# Sheet4.net
KiCad netlist of a schematic drawn in Altium Designer
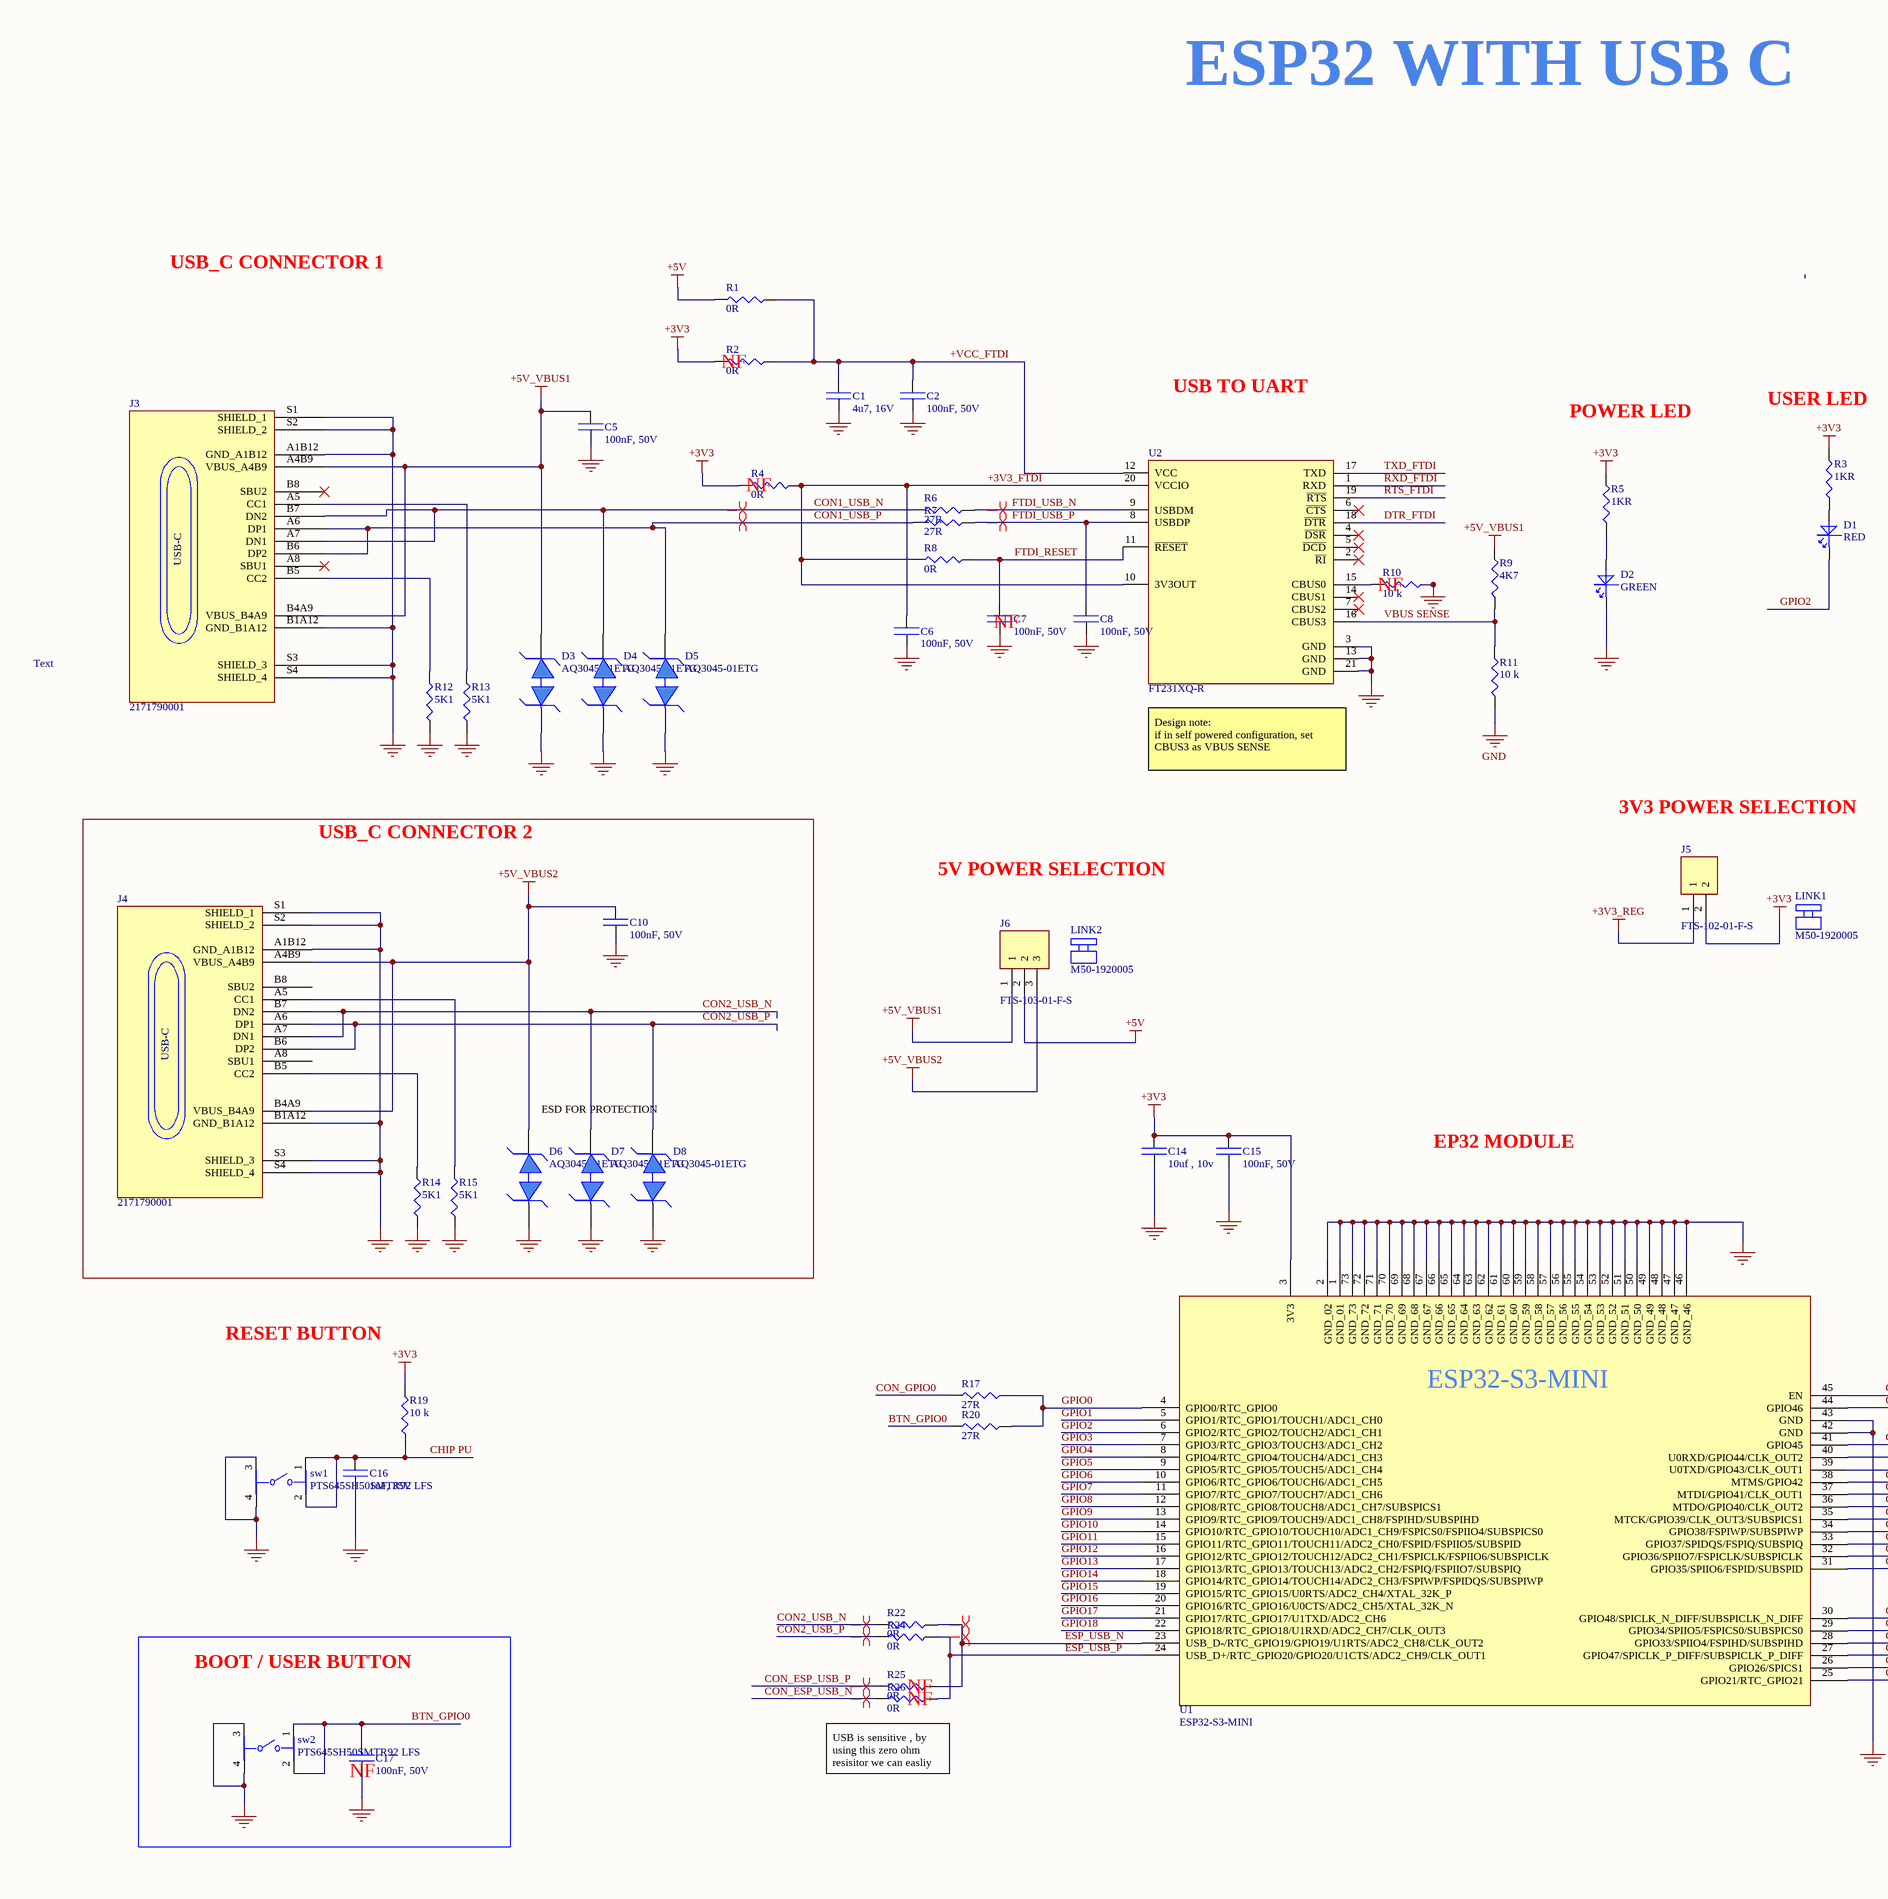
[diagram p0: Sheet4.SchDoc, left]
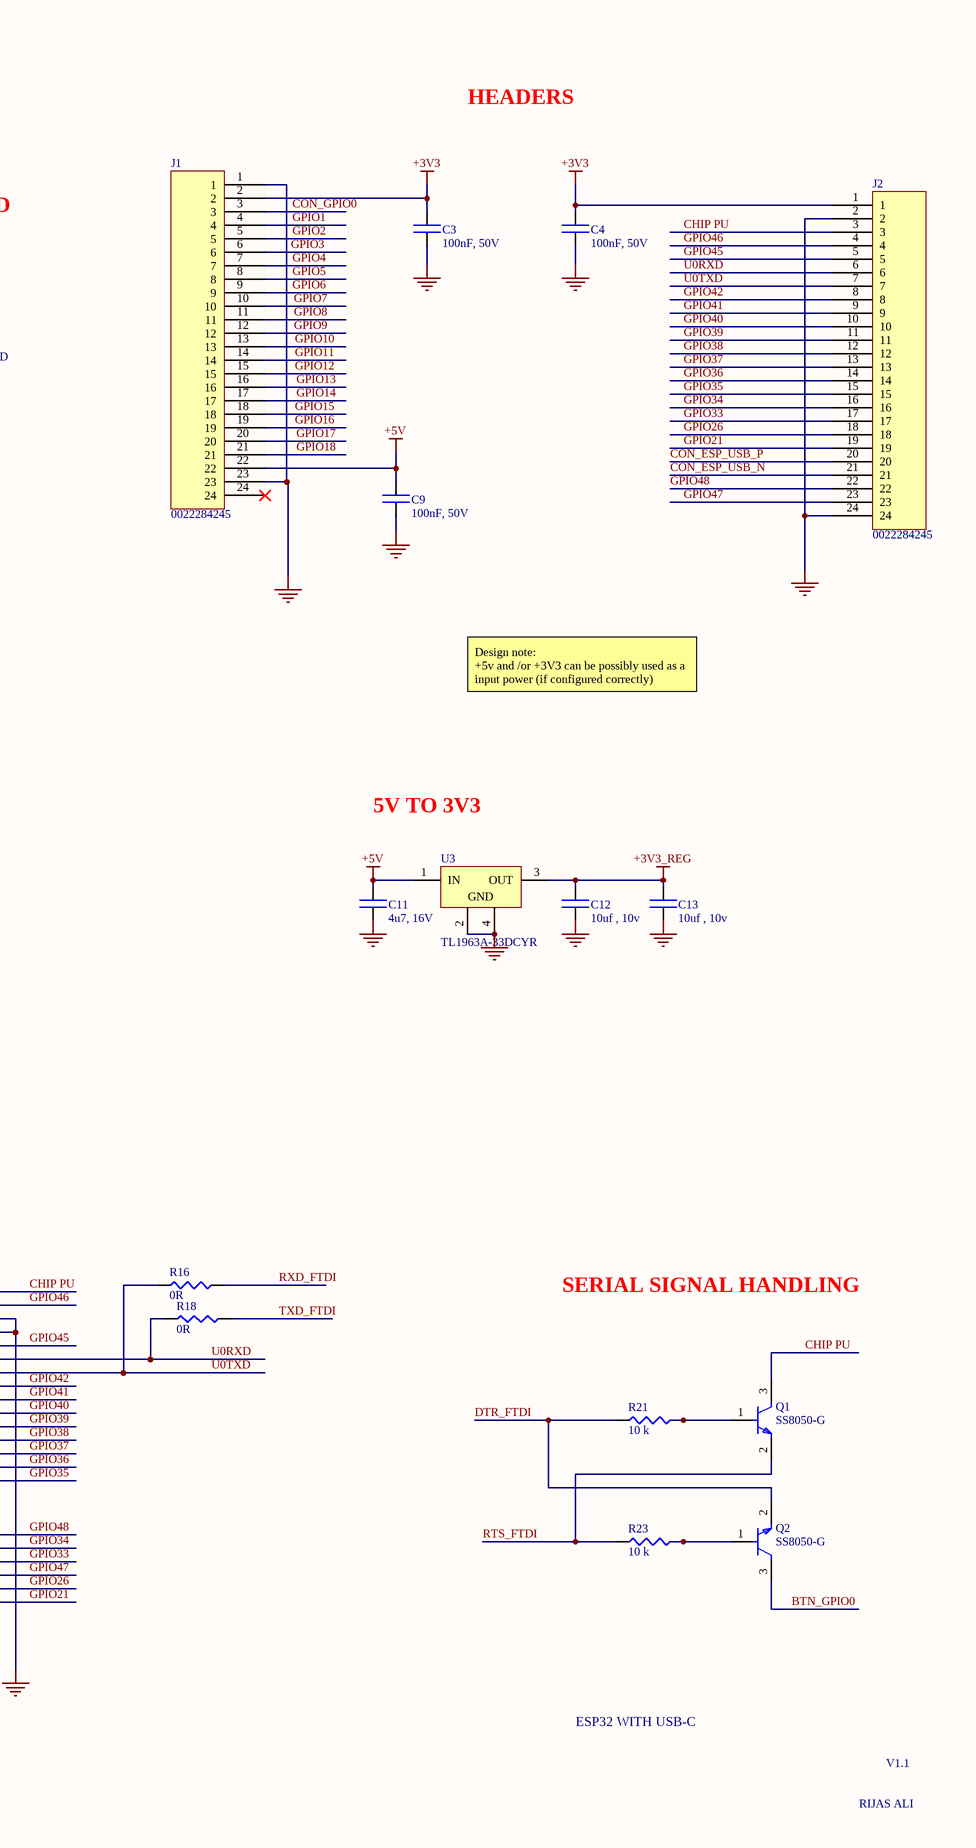
[diagram p1: Sheet4.SchDoc, right]

(export (version "E")
  (design (tool "Eeschema 10.0.6"))
  (components
    (comp (ref "C1")
      (value "4u7, 16V")
      (footprint "CAPC1005X55N")
      (description "4.7 µF ±20% 16V Ceramic Capacitor X5R 0402 (1005 Metric)")
      (fields
        (field (name "MANUFACTURER") "Samsung")
        (field (name "MANUFACTURER PART NUMBER") "CL05A475MO5NUNC")
      )
      (libsource (lib "ESP32 shematic library") (part "CL05A475MO5NUNC"))
    )
    (comp (ref "C2")
      (value "100nF, 50V")
      (footprint "CAPC1005X55N")
      (description "CAP CER 0.1UF 50V X7R 0402")
      (fields (field (name "MANUFACTURER") "Samsung") (field (name "TOLERANCE") "10%"))
      (libsource (lib "ESP32 shematic library") (part "CL05B104KB54PNC"))
    )
    (comp (ref "C3")
      (value "100nF, 50V")
      (footprint "CAPC1005X55N")
      (description "CAP CER 0.1UF 50V X7R 0402")
      (fields (field (name "MANUFACTURER") "Samsung") (field (name "TOLERANCE") "10%"))
      (libsource (lib "ESP32 shematic library") (part "CL05B104KB54PNC"))
    )
    (comp (ref "C4")
      (value "100nF, 50V")
      (footprint "CAPC1005X55N")
      (description "CAP CER 0.1UF 50V X7R 0402")
      (fields (field (name "MANUFACTURER") "Samsung") (field (name "TOLERANCE") "10%"))
      (libsource (lib "ESP32 shematic library") (part "CL05B104KB54PNC"))
    )
    (comp (ref "C5")
      (value "100nF, 50V")
      (footprint "CAPC1005X55N")
      (description "CAP CER 0.1UF 50V X7R 0402")
      (fields (field (name "MANUFACTURER") "Samsung") (field (name "TOLERANCE") "10%"))
      (libsource (lib "ESP32 shematic library") (part "CL05B104KB54PNC"))
    )
    (comp (ref "C6")
      (value "100nF, 50V")
      (footprint "CAPC1005X55N")
      (description "CAP CER 0.1UF 50V X7R 0402")
      (fields (field (name "MANUFACTURER") "Samsung") (field (name "TOLERANCE") "10%"))
      (libsource (lib "ESP32 shematic library") (part "CL05B104KB54PNC"))
    )
    (comp (ref "C7")
      (value "100nF, 50V")
      (footprint "CAPC1005X55N")
      (description "CAP CER 0.1UF 50V X7R 0402")
      (fields (field (name "MANUFACTURER") "Samsung") (field (name "TOLERANCE") "10%"))
      (libsource (lib "ESP32 shematic library") (part "CL05B104KB54PNC"))
    )
    (comp (ref "C8")
      (value "100nF, 50V")
      (footprint "CAPC1005X55N")
      (description "CAP CER 0.1UF 50V X7R 0402")
      (fields (field (name "MANUFACTURER") "Samsung") (field (name "TOLERANCE") "10%"))
      (libsource (lib "ESP32 shematic library") (part "CL05B104KB54PNC"))
    )
    (comp (ref "C9")
      (value "100nF, 50V")
      (footprint "CAPC1005X55N")
      (description "CAP CER 0.1UF 50V X7R 0402")
      (fields (field (name "MANUFACTURER") "Samsung") (field (name "TOLERANCE") "10%"))
      (libsource (lib "ESP32 shematic library") (part "CL05B104KB54PNC"))
    )
    (comp (ref "C10")
      (value "100nF, 50V")
      (footprint "CAPC1005X55N")
      (description "CAP CER 0.1UF 50V X7R 0402")
      (fields (field (name "MANUFACTURER") "Samsung") (field (name "TOLERANCE") "10%"))
      (libsource (lib "ESP32 shematic library") (part "CL05B104KB54PNC"))
    )
    (comp (ref "C11")
      (value "4u7, 16V")
      (footprint "CAPC1005X55N")
      (description "4.7 µF ±20% 16V Ceramic Capacitor X5R 0402 (1005 Metric)")
      (fields
        (field (name "MANUFACTURER") "Samsung")
        (field (name "MANUFACTURER PART NUMBER") "CL05A475MO5NUNC")
      )
      (libsource (lib "ESP32 shematic library") (part "CL05A475MO5NUNC"))
    )
    (comp (ref "C12")
      (value "10uf , 10v")
      (footprint "CAPC1005X55N")
      (description "10 µF ±20% 10V Ceramic Capacitor X5R 0402 (1005 Metric)")
      (fields (field (name "MANUFACTURER") "Samsung") (field (name "TOLERANCE") "20%"))
      (libsource (lib "ESP32 shematic library") (part "CL05A106MP8NUB8"))
    )
    (comp (ref "C13")
      (value "10uf , 10v")
      (footprint "CAPC1005X55N")
      (description "10 µF ±20% 10V Ceramic Capacitor X5R 0402 (1005 Metric)")
      (fields (field (name "MANUFACTURER") "Samsung") (field (name "TOLERANCE") "20%"))
      (libsource (lib "ESP32 shematic library") (part "CL05A106MP8NUB8"))
    )
    (comp (ref "C14")
      (value "10uf , 10v")
      (footprint "CAPC1005X55N")
      (description "10 µF ±20% 10V Ceramic Capacitor X5R 0402 (1005 Metric)")
      (fields (field (name "MANUFACTURER") "Samsung") (field (name "TOLERANCE") "20%"))
      (libsource (lib "ESP32 shematic library") (part "CL05A106MP8NUB8"))
    )
    (comp (ref "C15")
      (value "100nF, 50V")
      (footprint "CAPC1005X55N")
      (description "CAP CER 0.1UF 50V X7R 0402")
      (fields (field (name "MANUFACTURER") "Samsung") (field (name "TOLERANCE") "10%"))
      (libsource (lib "ESP32 shematic library") (part "CL05B104KB54PNC"))
    )
    (comp (ref "C16")
      (value "1uF, 35V")
      (footprint "CAPC1005X55N")
      (description "CAP CER 1UF 35V X5R 0402")
      (fields (field (name "MANUFACTURER") "Samsung") (field (name "TOLERANCE") "10%"))
      (libsource (lib "ESP32 shematic library") (part "CL05A105KL5NRNC"))
    )
    (comp (ref "C17")
      (value "100nF, 50V")
      (footprint "CAPC1005X55N")
      (description "CAP CER 0.1UF 50V X7R 0402")
      (fields (field (name "MANUFACTURER") "Samsung") (field (name "TOLERANCE") "10%"))
      (libsource (lib "ESP32 shematic library") (part "CL05B104KB54PNC"))
    )
    (comp (ref "D1")
      (value "RED")
      (footprint "Led Red")
      (description "LED RED 0402 SMD")
      (fields
        (field (name "MANUFACTURER") "Vishay")
        (field (name "MANUFACTURER PART NUMBER") "VLMS1500-GS08")
      )
      (libsource (lib "ESP32 shematic library") (part "VLMS1500-GS08"))
    )
    (comp (ref "D2")
      (value "GREEN")
      (footprint "Led green")
      (description "LED YLW-GRN 0402 SMD")
      (fields
        (field (name "MANUFACTURER") "Vishay")
        (field (name "MANUFACTURER PART NUMBER") "VLMG1500-GS08")
      )
      (libsource (lib "ESP32 shematic library") (part "VLMG1500-GS08"))
    )
    (comp (ref "D3")
      (value "AQ3045-01ETG")
      (footprint "SOD882")
      (description "TVS DIODE 5.3VWM 12VC SOD882")
      (fields (field (name "MANUFACTURER") "Littelfuse") (field (name "LCSC PART NUMBER") "C3710326"))
      (libsource (lib "ESP32 shematic library") (part "AQ3045-01ETG"))
    )
    (comp (ref "D4")
      (value "AQ3045-01ETG")
      (footprint "SOD882")
      (description "TVS DIODE 5.3VWM 12VC SOD882")
      (fields (field (name "MANUFACTURER") "Littelfuse") (field (name "LCSC PART NUMBER") "C3710326"))
      (libsource (lib "ESP32 shematic library") (part "AQ3045-01ETG"))
    )
    (comp (ref "D5")
      (value "AQ3045-01ETG")
      (footprint "SOD882")
      (description "TVS DIODE 5.3VWM 12VC SOD882")
      (fields (field (name "MANUFACTURER") "Littelfuse") (field (name "LCSC PART NUMBER") "C3710326"))
      (libsource (lib "ESP32 shematic library") (part "AQ3045-01ETG"))
    )
    (comp (ref "D6")
      (value "AQ3045-01ETG")
      (footprint "SOD882")
      (description "TVS DIODE 5.3VWM 12VC SOD882")
      (fields (field (name "MANUFACTURER") "Littelfuse") (field (name "LCSC PART NUMBER") "C3710326"))
      (libsource (lib "ESP32 shematic library") (part "AQ3045-01ETG"))
    )
    (comp (ref "D7")
      (value "AQ3045-01ETG")
      (footprint "SOD882")
      (description "TVS DIODE 5.3VWM 12VC SOD882")
      (fields (field (name "MANUFACTURER") "Littelfuse") (field (name "LCSC PART NUMBER") "C3710326"))
      (libsource (lib "ESP32 shematic library") (part "AQ3045-01ETG"))
    )
    (comp (ref "D8")
      (value "AQ3045-01ETG")
      (footprint "SOD882")
      (description "TVS DIODE 5.3VWM 12VC SOD882")
      (fields (field (name "MANUFACTURER") "Littelfuse") (field (name "LCSC PART NUMBER") "C3710326"))
      (libsource (lib "ESP32 shematic library") (part "AQ3045-01ETG"))
    )
    (comp (ref "J1")
      (value "0022284245")
      (footprint "HDR_1X24_2.5MM")
      (description "CONN HEADER VERT 24POS 2.54MM")
      (fields (field (name "MANUFACTURER") "Molex") (field (name "LCSC PART NUMBER") "C7145888"))
      (libsource (lib "ESP32 shematic library") (part "0022284245"))
    )
    (comp (ref "J2")
      (value "0022284245")
      (footprint "HDR_1X24_2.5MM")
      (description "CONN HEADER VERT 24POS 2.54MM")
      (fields (field (name "MANUFACTURER") "Molex") (field (name "LCSC PART NUMBER") "C7145888"))
      (libsource (lib "") (part "0022284245_1"))
    )
    (comp (ref "J3")
      (value "2171790001")
      (footprint "GCT_USB4105-GF-A")
      (description "CONN RCP USB2.0 TYP C 24P SMD RA")
      (fields (field (name "MANUFACTURER") "Molex") (field (name "MANUFACTURER PART NUMBER") "217179-0001"))
      (libsource (lib "ESP32 shematic library") (part "217179-0001"))
    )
    (comp (ref "J4")
      (value "2171790001")
      (footprint "GCT_USB4105-GF-A")
      (description "CONN RCP USB2.0 TYP C 24P SMD RA")
      (fields (field (name "MANUFACTURER") "Molex") (field (name "MANUFACTURER PART NUMBER") "217179-0001"))
      (libsource (lib "ESP32 shematic library") (part "217179-0001"))
    )
    (comp (ref "J5")
      (value "FTS-102-01-F-S")
      (footprint "HDR_1X2_1.27")
      (description "Conn Unshrouded Header HDR 2 POS 1.27mm Solder ST r")
      (fields (field (name "MANUFACTURER") "Samtec") (field (name "LCSC PART NUMBER") "C6045317"))
      (libsource (lib "ESP32 shematic library") (part "FTS-102-01-F-S"))
    )
    (comp (ref "J6")
      (value "FTS-103-01-F-S")
      (footprint "HDR_1X3_1.27")
      (description "CONN HEADER VERT 3POS 1.27MM")
      (fields (field (name "MANUFACTURER") "Samtec") (field (name "LCSC PART NUMBER") "C3333578"))
      (libsource (lib "ESP32 shematic library") (part "FTS-103-01-F-S"))
    )
    (comp (ref "LINK1")
      (value "M50-1920005")
      (description "CONN SHUNT 1.27MM RED CAP")
      (fields (field (name "MANUFACTURER") "Harwin") (field (name "LCSC PART NUMBER") "C6985646"))
      (libsource (lib "ESP32 shematic library") (part "M50-1920005"))
    )
    (comp (ref "LINK2")
      (value "M50-1920005")
      (description "CONN SHUNT 1.27MM RED CAP")
      (fields (field (name "MANUFACTURER") "Harwin") (field (name "LCSC PART NUMBER") "C6985646"))
      (libsource (lib "ESP32 shematic library") (part "M50-1920005"))
    )
    (comp (ref "Q1")
      (value "SS8050-G")
      (footprint "FP-SS8050-G-IPC_B")
      (description "Bipolar (BJT) Transistor NPN 25 V 1.5 A 100MHz 300 mW Surface Mount SOT-23-3")
      (fields (field (name "MANUFACTURER") "Comchip") (field (name "LCSC PART NUMBER") "C164886"))
      (libsource (lib "ESP32 shematic library") (part "SS8050-G"))
    )
    (comp (ref "Q2")
      (value "SS8050-G")
      (footprint "FP-SS8050-G-IPC_B")
      (description "Bipolar (BJT) Transistor NPN 25 V 1.5 A 100MHz 300 mW Surface Mount SOT-23-3")
      (fields (field (name "MANUFACTURER") "Comchip") (field (name "LCSC PART NUMBER") "C164886"))
      (libsource (lib "ESP32 shematic library") (part "SS8050-G"))
    )
    (comp (ref "R1")
      (value "0R")
      (footprint "RESC1005X37N")
      (description "RES 0 OHM JUMPER 1/16W 0402")
      (fields
        (field (name "MANUFACTURER") "Yageo")
        (field (name "MANUFACTURER PART NUMBER") "RC0402JR-070RL")
      )
      (libsource (lib "ESP32 shematic library") (part "RC0402JR-070RL"))
    )
    (comp (ref "R2")
      (value "0R")
      (footprint "RESC1005X37N")
      (description "RES 0 OHM JUMPER 1/16W 0402")
      (fields
        (field (name "MANUFACTURER") "Yageo")
        (field (name "MANUFACTURER PART NUMBER") "RC0402JR-070RL")
      )
      (libsource (lib "ESP32 shematic library") (part "RC0402JR-070RL"))
    )
    (comp (ref "R3")
      (value "1KR")
      (footprint "RESC1005X37N")
      (description "RES 1K OHM 1% 1/16W 0402")
      (fields
        (field (name "MANUFACTURER") "Yageo")
        (field (name "MANUFACTURER PART NUMBER") "RC0402FR-071KL")
      )
      (libsource (lib "ESP32 shematic library") (part "RC0402FR-071KL"))
    )
    (comp (ref "R4")
      (value "0R")
      (footprint "RESC1005X37N")
      (description "RES 0 OHM JUMPER 1/16W 0402")
      (fields
        (field (name "MANUFACTURER") "Yageo")
        (field (name "MANUFACTURER PART NUMBER") "RC0402JR-070RL")
      )
      (libsource (lib "ESP32 shematic library") (part "RC0402JR-070RL"))
    )
    (comp (ref "R5")
      (value "1KR")
      (footprint "RESC1005X37N")
      (description "RES 1K OHM 1% 1/16W 0402")
      (fields
        (field (name "MANUFACTURER") "Yageo")
        (field (name "MANUFACTURER PART NUMBER") "RC0402FR-071KL")
      )
      (libsource (lib "ESP32 shematic library") (part "RC0402FR-071KL"))
    )
    (comp (ref "R6")
      (value "27R")
      (footprint "RESC1005X37N")
      (description "RES 27 OHM 1% 1/16W 0402")
      (fields (field (name "MANUFACTURER") "Yageo") (field (name "TOLERANCE") "1%"))
      (libsource (lib "ESP32 shematic library") (part "RC0402FR-0727RL"))
    )
    (comp (ref "R7")
      (value "27R")
      (footprint "RESC1005X37N")
      (description "RES 27 OHM 1% 1/16W 0402")
      (fields (field (name "MANUFACTURER") "Yageo") (field (name "TOLERANCE") "1%"))
      (libsource (lib "ESP32 shematic library") (part "RC0402FR-0727RL"))
    )
    (comp (ref "R8")
      (value "0R")
      (footprint "RESC1005X37N")
      (description "RES 0 OHM JUMPER 1/16W 0402")
      (fields
        (field (name "MANUFACTURER") "Yageo")
        (field (name "MANUFACTURER PART NUMBER") "RC0402JR-070RL")
      )
      (libsource (lib "ESP32 shematic library") (part "RC0402JR-070RL"))
    )
    (comp (ref "R9")
      (value "4K7")
      (footprint "RESC1005X37N")
      (description "RES 4.7K OHM 1% 1/16W 0402")
      (fields
        (field (name "MANUFACTURER") "Yageo")
        (field (name "MANUFACTURER PART NUMBER") "RC0402FR-074K7L")
      )
      (libsource (lib "ESP32 shematic library") (part "RC0402FR-074K7L"))
    )
    (comp (ref "R10")
      (value "10 k")
      (footprint "RESC1005X37N")
      (description "RES SMD 10K OHM 1% 1/16W 0402")
      (fields (field (name "MANUFACTURER") "Yageo") (field (name "TOLERANCE") "1%"))
      (libsource (lib "ESP32 shematic library") (part "AC0402FR-0710KL"))
    )
    (comp (ref "R11")
      (value "10 k")
      (footprint "RESC1005X37N")
      (description "RES SMD 10K OHM 1% 1/16W 0402")
      (fields (field (name "MANUFACTURER") "Yageo") (field (name "TOLERANCE") "1%"))
      (libsource (lib "ESP32 shematic library") (part "AC0402FR-0710KL"))
    )
    (comp (ref "R12")
      (value "5K1")
      (footprint "RESC1005X37N")
      (description "RES SMD 5.1K OHM 1% 1/16W 0402")
      (fields (field (name "MANUFACTURER") "Yageo") (field (name "TOLERANCE") "1%"))
      (libsource (lib "ESP32 shematic library") (part "AC0402FR-075K1L"))
    )
    (comp (ref "R13")
      (value "5K1")
      (footprint "RESC1005X37N")
      (description "RES SMD 5.1K OHM 1% 1/16W 0402")
      (fields (field (name "MANUFACTURER") "Yageo") (field (name "TOLERANCE") "1%"))
      (libsource (lib "ESP32 shematic library") (part "AC0402FR-075K1L"))
    )
    (comp (ref "R14")
      (value "5K1")
      (footprint "RESC1005X37N")
      (description "RES SMD 5.1K OHM 1% 1/16W 0402")
      (fields (field (name "MANUFACTURER") "Yageo") (field (name "TOLERANCE") "1%"))
      (libsource (lib "ESP32 shematic library") (part "AC0402FR-075K1L"))
    )
    (comp (ref "R15")
      (value "5K1")
      (footprint "RESC1005X37N")
      (description "RES SMD 5.1K OHM 1% 1/16W 0402")
      (fields (field (name "MANUFACTURER") "Yageo") (field (name "TOLERANCE") "1%"))
      (libsource (lib "ESP32 shematic library") (part "AC0402FR-075K1L"))
    )
    (comp (ref "R16")
      (value "0R")
      (footprint "RESC1005X37N")
      (description "RES 0 OHM JUMPER 1/16W 0402")
      (fields
        (field (name "MANUFACTURER") "Yageo")
        (field (name "MANUFACTURER PART NUMBER") "RC0402JR-070RL")
      )
      (libsource (lib "ESP32 shematic library") (part "RC0402JR-070RL"))
    )
    (comp (ref "R17")
      (value "27R")
      (footprint "RESC1005X37N")
      (description "RES 27 OHM 1% 1/16W 0402")
      (fields (field (name "MANUFACTURER") "Yageo") (field (name "TOLERANCE") "1%"))
      (libsource (lib "ESP32 shematic library") (part "RC0402FR-0727RL"))
    )
    (comp (ref "R18")
      (value "0R")
      (footprint "RESC1005X37N")
      (description "RES 0 OHM JUMPER 1/16W 0402")
      (fields
        (field (name "MANUFACTURER") "Yageo")
        (field (name "MANUFACTURER PART NUMBER") "RC0402JR-070RL")
      )
      (libsource (lib "ESP32 shematic library") (part "RC0402JR-070RL"))
    )
    (comp (ref "R19")
      (value "10 k")
      (footprint "RESC1005X37N")
      (description "RES SMD 10K OHM 1% 1/16W 0402")
      (fields (field (name "MANUFACTURER") "Yageo") (field (name "TOLERANCE") "1%"))
      (libsource (lib "ESP32 shematic library") (part "AC0402FR-0710KL"))
    )
    (comp (ref "R20")
      (value "27R")
      (footprint "RESC1005X37N")
      (description "RES 27 OHM 1% 1/16W 0402")
      (fields (field (name "MANUFACTURER") "Yageo") (field (name "TOLERANCE") "1%"))
      (libsource (lib "ESP32 shematic library") (part "RC0402FR-0727RL"))
    )
    (comp (ref "R21")
      (value "10 k")
      (footprint "RESC1005X37N")
      (description "RES SMD 10K OHM 1% 1/16W 0402")
      (fields (field (name "MANUFACTURER") "Yageo") (field (name "TOLERANCE") "1%"))
      (libsource (lib "ESP32 shematic library") (part "AC0402FR-0710KL"))
    )
    (comp (ref "R22")
      (value "0R")
      (footprint "RESC1005X37N")
      (description "RES 0 OHM JUMPER 1/16W 0402")
      (fields
        (field (name "MANUFACTURER") "Yageo")
        (field (name "MANUFACTURER PART NUMBER") "RC0402JR-070RL")
      )
      (libsource (lib "ESP32 shematic library") (part "RC0402JR-070RL"))
    )
    (comp (ref "R23")
      (value "10 k")
      (footprint "RESC1005X37N")
      (description "RES SMD 10K OHM 1% 1/16W 0402")
      (fields (field (name "MANUFACTURER") "Yageo") (field (name "TOLERANCE") "1%"))
      (libsource (lib "ESP32 shematic library") (part "AC0402FR-0710KL"))
    )
    (comp (ref "R24")
      (value "0R")
      (footprint "RESC1005X37N")
      (description "RES 0 OHM JUMPER 1/16W 0402")
      (fields
        (field (name "MANUFACTURER") "Yageo")
        (field (name "MANUFACTURER PART NUMBER") "RC0402JR-070RL")
      )
      (libsource (lib "ESP32 shematic library") (part "RC0402JR-070RL"))
    )
    (comp (ref "R25")
      (value "0R")
      (footprint "RESC1005X37N")
      (description "RES 0 OHM JUMPER 1/16W 0402")
      (fields
        (field (name "MANUFACTURER") "Yageo")
        (field (name "MANUFACTURER PART NUMBER") "RC0402JR-070RL")
      )
      (libsource (lib "ESP32 shematic library") (part "RC0402JR-070RL"))
    )
    (comp (ref "R26")
      (value "0R")
      (footprint "RESC1005X37N")
      (description "RES 0 OHM JUMPER 1/16W 0402")
      (fields
        (field (name "MANUFACTURER") "Yageo")
        (field (name "MANUFACTURER PART NUMBER") "RC0402JR-070RL")
      )
      (libsource (lib "ESP32 shematic library") (part "RC0402JR-070RL"))
    )
    (comp (ref "sw1")
      (value "PTS645SH50SMTR92 LFS")
      (footprint "FP-PTS645SH50SMTR92LFS-MFG")
      (description "SWITCH TACTILE SPST-NO 0.05A 12V")
      (fields (field (name "MANUFACTURER") "ITT C&K") (field (name "LCSC PART NUMBER") "C221869"))
      (libsource (lib "ESP32 shematic library") (part "PTS645SH50SMTR92LFS"))
    )
    (comp (ref "sw2")
      (value "PTS645SH50SMTR92 LFS")
      (footprint "FP-PTS645SH50SMTR92LFS-MFG")
      (description "SWITCH TACTILE SPST-NO 0.05A 12V")
      (fields (field (name "MANUFACTURER") "ITT C&K") (field (name "LCSC PART NUMBER") "C221869"))
      (libsource (lib "ESP32 shematic library") (part "PTS645SH50SMTR92LFS"))
    )
    (comp (ref "U1")
      (value "ESP32-S3-MINI")
      (footprint "XCVR_ESP32-S3-MINI-1-N8")
      (description "SMD module, ESP32-S3FN8, 8 MB SPI flash, PCB antenna")
      (fields (field (name "MANUFACTURER") "Espressif Systems") (field (name "LCSC PART NUMBER") "C2913206"))
      (libsource (lib "ESP32 shematic library") (part "ESP32-S3-MINI-1-N8"))
    )
    (comp (ref "U2")
      (value "FT231XQ-R")
      (footprint "FP-QFN-20-IPC_B")
      (description "USB Bridge, USB to UART USB 2.0 UART Interface 20-QFN (4x4)")
      (fields (field (name "MANUFACTURER") "FTDI") (field (name "LCSC PART NUMBER") "C132159"))
      (libsource (lib "ESP32 shematic library") (part "FT231XQ-R"))
    )
    (comp (ref "U3")
      (value "TL1963A-33DCYR")
      (footprint "DCY0004A_N")
      (description "IC REG LINEAR 3.3V 1.5A SOT223-4")
      (fields (field (name "MANUFACTURER") "Texas Instruments") (field (name "LCSC PART NUMBER") "C181262"))
      (libsource (lib "ESP32 shematic library") (part "TL1963A-33DCYR"))
    )
  )
  (nets
    (net (code "1") (name "+3V3") (class "Default")
      (node (ref "C14") (pin "2") (pinfunction "2_2") (pintype "passive"))
      (node (ref "C15") (pin "2") (pinfunction "2_2") (pintype "passive"))
      (node (ref "C3") (pin "2") (pinfunction "2_2") (pintype "passive"))
      (node (ref "C4") (pin "2") (pinfunction "2_2") (pintype "passive"))
      (node (ref "J1") (pin "2") (pinfunction "2_2") (pintype "passive"))
      (node (ref "J2") (pin "1") (pinfunction "1_1") (pintype "passive"))
      (node (ref "J5") (pin "2") (pinfunction "2_2") (pintype "passive"))
      (node (ref "R19") (pin "2") (pinfunction "2_2") (pintype "passive"))
      (node (ref "R2") (pin "1") (pinfunction "1_1") (pintype "passive"))
      (node (ref "R3") (pin "2") (pinfunction "2_2") (pintype "passive"))
      (node (ref "R4") (pin "1") (pinfunction "1_1") (pintype "passive"))
      (node (ref "R5") (pin "2") (pinfunction "2_2") (pintype "passive"))
      (node (ref "U1") (pin "3") (pinfunction "3V3_3") (pintype "passive"))
    )
    (net (code "2") (name "+3V3_REG") (class "Default")
      (node (ref "C12") (pin "2") (pinfunction "2_2") (pintype "passive"))
      (node (ref "C13") (pin "2") (pinfunction "2_2") (pintype "passive"))
      (node (ref "J5") (pin "1") (pinfunction "1_1") (pintype "passive"))
      (node (ref "U3") (pin "3") (pinfunction "OUT_3") (pintype "power_in"))
    )
    (net (code "3") (name "+5V") (class "Default")
      (node (ref "C11") (pin "2") (pinfunction "2_2") (pintype "passive"))
      (node (ref "C9") (pin "2") (pinfunction "2_2") (pintype "passive"))
      (node (ref "J1") (pin "22") (pinfunction "22_22") (pintype "passive"))
      (node (ref "J6") (pin "2") (pinfunction "2_2") (pintype "passive"))
      (node (ref "R1") (pin "1") (pinfunction "1_1") (pintype "passive"))
      (node (ref "U3") (pin "1") (pinfunction "IN_1") (pintype "power_in"))
    )
    (net (code "4") (name "+5V_VBUS1") (class "Default")
      (node (ref "C5") (pin "2") (pinfunction "2_2") (pintype "passive"))
      (node (ref "D3") (pin "2") (pinfunction "2_2") (pintype "passive"))
      (node (ref "J3") (pin "A4B9") (pinfunction "VBUS_A4B9_A4B9") (pintype "passive"))
      (node (ref "J3") (pin "B4A9") (pinfunction "VBUS_B4A9_B4A9") (pintype "passive"))
      (node (ref "J6") (pin "1") (pinfunction "1_1") (pintype "passive"))
      (node (ref "R9") (pin "2") (pinfunction "2_2") (pintype "passive"))
    )
    (net (code "5") (name "+5V_VBUS2") (class "Default")
      (node (ref "C10") (pin "2") (pinfunction "2_2") (pintype "passive"))
      (node (ref "D6") (pin "2") (pinfunction "2_2") (pintype "passive"))
      (node (ref "J4") (pin "A4B9") (pinfunction "VBUS_A4B9_A4B9") (pintype "passive"))
      (node (ref "J4") (pin "B4A9") (pinfunction "VBUS_B4A9_B4A9") (pintype "passive"))
      (node (ref "J6") (pin "3") (pinfunction "3_3") (pintype "passive"))
    )
    (net (code "6") (name "/+3V3_FTDI") (class "Default")
      (node (ref "C6") (pin "2") (pinfunction "2_2") (pintype "passive"))
      (node (ref "R4") (pin "2") (pinfunction "2_2") (pintype "passive"))
      (node (ref "R8") (pin "1") (pinfunction "1_1") (pintype "passive"))
      (node (ref "U2") (pin "10") (pinfunction "3V3OUT_10") (pintype "passive"))
      (node (ref "U2") (pin "20") (pinfunction "VCCIO_20") (pintype "passive"))
    )
    (net (code "7") (name "/+VCC_FTDI") (class "Default")
      (node (ref "C1") (pin "2") (pinfunction "2_2") (pintype "passive"))
      (node (ref "C2") (pin "2") (pinfunction "2_2") (pintype "passive"))
      (node (ref "R1") (pin "2") (pinfunction "2_2") (pintype "passive"))
      (node (ref "R2") (pin "2") (pinfunction "2_2") (pintype "passive"))
      (node (ref "U2") (pin "12") (pinfunction "VCC_12") (pintype "passive"))
    )
    (net (code "8") (name "/BTN_GPIO0") (class "Default")
      (node (ref "C17") (pin "2") (pinfunction "2_2") (pintype "passive"))
      (node (ref "Q2") (pin "3") (pinfunction "C_3") (pintype "passive"))
      (node (ref "R20") (pin "1") (pinfunction "1_1") (pintype "passive"))
      (node (ref "sw2") (pin "1") (pinfunction "1_1") (pintype "passive"))
      (node (ref "sw2") (pin "2") (pinfunction "2_2") (pintype "passive"))
    )
    (net (code "9") (name "/CHIP PU") (class "Default")
      (node (ref "C16") (pin "2") (pinfunction "2_2") (pintype "passive"))
      (node (ref "J2") (pin "3") (pinfunction "3_3") (pintype "passive"))
      (node (ref "Q1") (pin "3") (pinfunction "C_3") (pintype "passive"))
      (node (ref "R19") (pin "1") (pinfunction "1_1") (pintype "passive"))
      (node (ref "U1") (pin "45") (pinfunction "EN_45") (pintype "passive"))
      (node (ref "sw1") (pin "1") (pinfunction "1_1") (pintype "passive"))
      (node (ref "sw1") (pin "2") (pinfunction "2_2") (pintype "passive"))
    )
    (net (code "10") (name "/CON1_USB_N") (class "Default")
      (node (ref "D4") (pin "2") (pinfunction "2_2") (pintype "passive"))
      (node (ref "J3") (pin "A7") (pinfunction "DN1_A7") (pintype "passive"))
      (node (ref "J3") (pin "B7") (pinfunction "DN2_B7") (pintype "passive"))
      (node (ref "R6") (pin "1") (pinfunction "1_1") (pintype "passive"))
    )
    (net (code "11") (name "/CON1_USB_P") (class "Default")
      (node (ref "D5") (pin "2") (pinfunction "2_2") (pintype "passive"))
      (node (ref "J3") (pin "A6") (pinfunction "DP1_A6") (pintype "passive"))
      (node (ref "J3") (pin "B6") (pinfunction "DP2_B6") (pintype "passive"))
      (node (ref "R7") (pin "1") (pinfunction "1_1") (pintype "passive"))
    )
    (net (code "12") (name "/CON2_USB_N") (class "Default")
      (node (ref "D7") (pin "2") (pinfunction "2_2") (pintype "passive"))
      (node (ref "J4") (pin "A7") (pinfunction "DN1_A7") (pintype "passive"))
      (node (ref "J4") (pin "B7") (pinfunction "DN2_B7") (pintype "passive"))
      (node (ref "R22") (pin "1") (pinfunction "1_1") (pintype "passive"))
    )
    (net (code "13") (name "/CON2_USB_P") (class "Default")
      (node (ref "D8") (pin "2") (pinfunction "2_2") (pintype "passive"))
      (node (ref "J4") (pin "A6") (pinfunction "DP1_A6") (pintype "passive"))
      (node (ref "J4") (pin "B6") (pinfunction "DP2_B6") (pintype "passive"))
      (node (ref "R24") (pin "1") (pinfunction "1_1") (pintype "passive"))
    )
    (net (code "14") (name "/CON_ESP_USB_N") (class "Default")
      (node (ref "J2") (pin "21") (pinfunction "21_21") (pintype "passive"))
      (node (ref "R26") (pin "1") (pinfunction "1_1") (pintype "passive"))
    )
    (net (code "15") (name "/CON_ESP_USB_P") (class "Default")
      (node (ref "J2") (pin "20") (pinfunction "20_20") (pintype "passive"))
      (node (ref "R25") (pin "1") (pinfunction "1_1") (pintype "passive"))
    )
    (net (code "16") (name "/CON_GPIO0") (class "Default")
      (node (ref "J1") (pin "3") (pinfunction "3_3") (pintype "passive"))
      (node (ref "R17") (pin "1") (pinfunction "1_1") (pintype "passive"))
    )
    (net (code "17") (name "/DTR_FTDI") (class "Default")
      (node (ref "Q2") (pin "2") (pinfunction "E_2") (pintype "passive"))
      (node (ref "R21") (pin "2") (pinfunction "2_2") (pintype "passive"))
      (node (ref "U2") (pin "18") (pinfunction "~{DTR}_18") (pintype "passive"))
    )
    (net (code "18") (name "/ESP_USB_N") (class "Default")
      (node (ref "R22") (pin "2") (pinfunction "2_2") (pintype "passive"))
      (node (ref "R25") (pin "2") (pinfunction "2_2") (pintype "passive"))
      (node (ref "U1") (pin "23") (pinfunction "USB_D-/RTC_GPIO19/GPIO19/U1RTS/ADC2_CH8/CLK_OUT2_23") (pintype "passive"))
    )
    (net (code "19") (name "/ESP_USB_P") (class "Default")
      (node (ref "R24") (pin "2") (pinfunction "2_2") (pintype "passive"))
      (node (ref "R26") (pin "2") (pinfunction "2_2") (pintype "passive"))
      (node (ref "U1") (pin "24") (pinfunction "USB_D+/RTC_GPIO20/GPIO20/U1CTS/ADC2_CH9/CLK_OUT1_24") (pintype "passive"))
    )
    (net (code "20") (name "/FTDI_RESET") (class "Default")
      (node (ref "C7") (pin "2") (pinfunction "2_2") (pintype "passive"))
      (node (ref "R8") (pin "2") (pinfunction "2_2") (pintype "passive"))
      (node (ref "U2") (pin "11") (pinfunction "~{RESET}_11") (pintype "passive"))
    )
    (net (code "21") (name "/FTDI_USB_N") (class "Default")
      (node (ref "R6") (pin "2") (pinfunction "2_2") (pintype "passive"))
      (node (ref "U2") (pin "9") (pinfunction "USBDM_9") (pintype "passive"))
    )
    (net (code "22") (name "/FTDI_USB_P") (class "Default")
      (node (ref "C8") (pin "2") (pinfunction "2_2") (pintype "passive"))
      (node (ref "R7") (pin "2") (pinfunction "2_2") (pintype "passive"))
      (node (ref "U2") (pin "8") (pinfunction "USBDP_8") (pintype "passive"))
    )
    (net (code "23") (name "/GPIO0") (class "Default")
      (node (ref "R17") (pin "2") (pinfunction "2_2") (pintype "passive"))
      (node (ref "R20") (pin "2") (pinfunction "2_2") (pintype "passive"))
      (node (ref "U1") (pin "4") (pinfunction "GPIO0/RTC_GPIO0_4") (pintype "passive"))
    )
    (net (code "24") (name "/GPIO1") (class "Default")
      (node (ref "J1") (pin "4") (pinfunction "4_4") (pintype "passive"))
      (node (ref "U1") (pin "5") (pinfunction "GPIO1/RTC_GPIO1/TOUCH1/ADC1_CH0_5") (pintype "passive"))
    )
    (net (code "25") (name "/GPIO2") (class "Default")
      (node (ref "D1") (pin "1") (pinfunction "1_1") (pintype "passive"))
      (node (ref "J1") (pin "5") (pinfunction "5_5") (pintype "passive"))
      (node (ref "U1") (pin "6") (pinfunction "GPIO2/RTC_GPIO2/TOUCH2/ADC1_CH1_6") (pintype "passive"))
    )
    (net (code "26") (name "/GPIO3") (class "Default")
      (node (ref "J1") (pin "6") (pinfunction "6_6") (pintype "passive"))
      (node (ref "U1") (pin "7") (pinfunction "GPIO3/RTC_GPIO3/TOUCH3/ADC1_CH2_7") (pintype "passive"))
    )
    (net (code "27") (name "/GPIO4") (class "Default")
      (node (ref "J1") (pin "7") (pinfunction "7_7") (pintype "passive"))
      (node (ref "U1") (pin "8") (pinfunction "GPIO4/RTC_GPIO4/TOUCH4/ADC1_CH3_8") (pintype "passive"))
    )
    (net (code "28") (name "/GPIO5") (class "Default")
      (node (ref "J1") (pin "8") (pinfunction "8_8") (pintype "passive"))
      (node (ref "U1") (pin "9") (pinfunction "GPIO5/RTC_GPIO5/TOUCH5/ADC1_CH4_9") (pintype "passive"))
    )
    (net (code "29") (name "/GPIO6") (class "Default")
      (node (ref "J1") (pin "9") (pinfunction "9_9") (pintype "passive"))
      (node (ref "U1") (pin "10") (pinfunction "GPIO6/RTC_GPIO6/TOUCH6/ADC1_CH5_10") (pintype "passive"))
    )
    (net (code "30") (name "/GPIO7") (class "Default")
      (node (ref "J1") (pin "10") (pinfunction "10_10") (pintype "passive"))
      (node (ref "U1") (pin "11") (pinfunction "GPIO7/RTC_GPIO7/TOUCH7/ADC1_CH6_11") (pintype "passive"))
    )
    (net (code "31") (name "/GPIO8") (class "Default")
      (node (ref "J1") (pin "11") (pinfunction "11_11") (pintype "passive"))
      (node (ref "U1") (pin "12") (pinfunction "GPIO8/RTC_GPIO8/TOUCH8/ADC1_CH7/SUBSPICS1_12") (pintype "passive"))
    )
    (net (code "32") (name "/GPIO9") (class "Default")
      (node (ref "J1") (pin "12") (pinfunction "12_12") (pintype "passive"))
      (node (ref "U1") (pin "13") (pinfunction "GPIO9/RTC_GPIO9/TOUCH9/ADC1_CH8/FSPIHD/SUBSPIHD_13") (pintype "passive"))
    )
    (net (code "33") (name "/GPIO10") (class "Default")
      (node (ref "J1") (pin "13") (pinfunction "13_13") (pintype "passive"))
      (node (ref "U1") (pin "14") (pinfunction "GPIO10/RTC_GPIO10/TOUCH10/ADC1_CH9/FSPICS0/FSPIIO4/SUBSPICS0_14") (pintype "passive"))
    )
    (net (code "34") (name "/GPIO11") (class "Default")
      (node (ref "J1") (pin "14") (pinfunction "14_14") (pintype "passive"))
      (node (ref "U1") (pin "15") (pinfunction "GPIO11/RTC_GPIO11/TOUCH11/ADC2_CH0/FSPID/FSPIIO5/SUBSPID_15") (pintype "passive"))
    )
    (net (code "35") (name "/GPIO12") (class "Default")
      (node (ref "J1") (pin "15") (pinfunction "15_15") (pintype "passive"))
      (node (ref "U1") (pin "16") (pinfunction "GPIO12/RTC_GPIO12/TOUCH12/ADC2_CH1/FSPICLK/FSPIIO6/SUBSPICLK_16") (pintype "passive"))
    )
    (net (code "36") (name "/GPIO13") (class "Default")
      (node (ref "J1") (pin "16") (pinfunction "16_16") (pintype "passive"))
      (node (ref "U1") (pin "17") (pinfunction "GPIO13/RTC_GPIO13/TOUCH13/ADC2_CH2/FSPIQ/FSPIIO7/SUBSPIQ_17") (pintype "passive"))
    )
    (net (code "37") (name "/GPIO14") (class "Default")
      (node (ref "J1") (pin "17") (pinfunction "17_17") (pintype "passive"))
      (node (ref "U1") (pin "18") (pinfunction "GPIO14/RTC_GPIO14/TOUCH14/ADC2_CH3/FSPIWP/FSPIDQS/SUBSPIWP_18") (pintype "passive"))
    )
    (net (code "38") (name "/GPIO15") (class "Default")
      (node (ref "J1") (pin "18") (pinfunction "18_18") (pintype "passive"))
      (node (ref "U1") (pin "19") (pinfunction "GPIO15/RTC_GPIO15/U0RTS/ADC2_CH4/XTAL_32K_P_19") (pintype "passive"))
    )
    (net (code "39") (name "/GPIO16") (class "Default")
      (node (ref "J1") (pin "19") (pinfunction "19_19") (pintype "passive"))
      (node (ref "U1") (pin "20") (pinfunction "GPIO16/RTC_GPIO16/U0CTS/ADC2_CH5/XTAL_32K_N_20") (pintype "passive"))
    )
    (net (code "40") (name "/GPIO17") (class "Default")
      (node (ref "J1") (pin "20") (pinfunction "20_20") (pintype "passive"))
      (node (ref "U1") (pin "21") (pinfunction "GPIO17/RTC_GPIO17/U1TXD/ADC2_CH6_21") (pintype "passive"))
    )
    (net (code "41") (name "/GPIO18") (class "Default")
      (node (ref "J1") (pin "21") (pinfunction "21_21") (pintype "passive"))
      (node (ref "U1") (pin "22") (pinfunction "GPIO18/RTC_GPIO18/U1RXD/ADC2_CH7/CLK_OUT3_22") (pintype "passive"))
    )
    (net (code "42") (name "/GPIO21") (class "Default")
      (node (ref "J2") (pin "19") (pinfunction "19_19") (pintype "passive"))
      (node (ref "U1") (pin "25") (pinfunction "GPIO21/RTC_GPIO21_25") (pintype "passive"))
    )
    (net (code "43") (name "/GPIO26") (class "Default")
      (node (ref "J2") (pin "18") (pinfunction "18_18") (pintype "passive"))
      (node (ref "U1") (pin "26") (pinfunction "GPIO26/SPICS1_26") (pintype "passive"))
    )
    (net (code "44") (name "/GPIO33") (class "Default")
      (node (ref "J2") (pin "17") (pinfunction "17_17") (pintype "passive"))
      (node (ref "U1") (pin "28") (pinfunction "GPIO33/SPIIO4/FSPIHD/SUBSPIHD_28") (pintype "passive"))
    )
    (net (code "45") (name "/GPIO34") (class "Default")
      (node (ref "J2") (pin "16") (pinfunction "16_16") (pintype "passive"))
      (node (ref "U1") (pin "29") (pinfunction "GPIO34/SPIIO5/FSPICS0/SUBSPICS0_29") (pintype "passive"))
    )
    (net (code "46") (name "/GPIO35") (class "Default")
      (node (ref "J2") (pin "15") (pinfunction "15_15") (pintype "passive"))
      (node (ref "U1") (pin "31") (pinfunction "GPIO35/SPIIO6/FSPID/SUBSPID_31") (pintype "passive"))
    )
    (net (code "47") (name "/GPIO36") (class "Default")
      (node (ref "J2") (pin "14") (pinfunction "14_14") (pintype "passive"))
      (node (ref "U1") (pin "32") (pinfunction "GPIO36/SPIIO7/FSPICLK/SUBSPICLK_32") (pintype "passive"))
    )
    (net (code "48") (name "/GPIO37") (class "Default")
      (node (ref "J2") (pin "13") (pinfunction "13_13") (pintype "passive"))
      (node (ref "U1") (pin "33") (pinfunction "GPIO37/SPIDQS/FSPIQ/SUBSPIQ_33") (pintype "passive"))
    )
    (net (code "49") (name "/GPIO38") (class "Default")
      (node (ref "J2") (pin "12") (pinfunction "12_12") (pintype "passive"))
      (node (ref "U1") (pin "34") (pinfunction "GPIO38/FSPIWP/SUBSPIWP_34") (pintype "passive"))
    )
    (net (code "50") (name "/GPIO39") (class "Default")
      (node (ref "J2") (pin "11") (pinfunction "11_11") (pintype "passive"))
      (node (ref "U1") (pin "35") (pinfunction "MTCK/GPIO39/CLK_OUT3/SUBSPICS1_35") (pintype "passive"))
    )
    (net (code "51") (name "/GPIO40") (class "Default")
      (node (ref "J2") (pin "10") (pinfunction "10_10") (pintype "passive"))
      (node (ref "U1") (pin "36") (pinfunction "MTDO/GPIO40/CLK_OUT2_36") (pintype "passive"))
    )
    (net (code "52") (name "/GPIO41") (class "Default")
      (node (ref "J2") (pin "9") (pinfunction "9_9") (pintype "passive"))
      (node (ref "U1") (pin "37") (pinfunction "MTDI/GPIO41/CLK_OUT1_37") (pintype "passive"))
    )
    (net (code "53") (name "/GPIO42") (class "Default")
      (node (ref "J2") (pin "8") (pinfunction "8_8") (pintype "passive"))
      (node (ref "U1") (pin "38") (pinfunction "MTMS/GPIO42_38") (pintype "passive"))
    )
    (net (code "54") (name "/GPIO45") (class "Default")
      (node (ref "J2") (pin "5") (pinfunction "5_5") (pintype "passive"))
      (node (ref "U1") (pin "41") (pinfunction "GPIO45_41") (pintype "passive"))
    )
    (net (code "55") (name "/GPIO46") (class "Default")
      (node (ref "J2") (pin "4") (pinfunction "4_4") (pintype "passive"))
      (node (ref "U1") (pin "44") (pinfunction "GPIO46_44") (pintype "passive"))
    )
    (net (code "56") (name "/GPIO47") (class "Default")
      (node (ref "J2") (pin "23") (pinfunction "23_23") (pintype "passive"))
      (node (ref "U1") (pin "27") (pinfunction "GPIO47/SPICLK_P_DIFF/SUBSPICLK_P_DIFF_27") (pintype "passive"))
    )
    (net (code "57") (name "/GPIO48") (class "Default")
      (node (ref "J2") (pin "22") (pinfunction "22_22") (pintype "passive"))
      (node (ref "U1") (pin "30") (pinfunction "GPIO48/SPICLK_N_DIFF/SUBSPICLK_N_DIFF_30") (pintype "passive"))
    )
    (net (code "58") (name "/RTS_FTDI") (class "Default")
      (node (ref "Q1") (pin "2") (pinfunction "E_2") (pintype "passive"))
      (node (ref "R23") (pin "2") (pinfunction "2_2") (pintype "passive"))
      (node (ref "U2") (pin "19") (pinfunction "~{RTS}_19") (pintype "passive"))
    )
    (net (code "59") (name "/RXD_FTDI") (class "Default")
      (node (ref "R16") (pin "2") (pinfunction "2_2") (pintype "passive"))
      (node (ref "U2") (pin "1") (pinfunction "RXD_1") (pintype "passive"))
    )
    (net (code "60") (name "/TXD_FTDI") (class "Default")
      (node (ref "R18") (pin "2") (pinfunction "2_2") (pintype "passive"))
      (node (ref "U2") (pin "17") (pinfunction "TXD_17") (pintype "passive"))
    )
    (net (code "61") (name "/U0RXD") (class "Default")
      (node (ref "J2") (pin "6") (pinfunction "6_6") (pintype "passive"))
      (node (ref "R18") (pin "1") (pinfunction "1_1") (pintype "passive"))
      (node (ref "U1") (pin "40") (pinfunction "U0RXD/GPIO44/CLK_OUT2_40") (pintype "passive"))
    )
    (net (code "62") (name "/U0TXD") (class "Default")
      (node (ref "J2") (pin "7") (pinfunction "7_7") (pintype "passive"))
      (node (ref "R16") (pin "1") (pinfunction "1_1") (pintype "passive"))
      (node (ref "U1") (pin "39") (pinfunction "U0TXD/GPIO43/CLK_OUT1_39") (pintype "passive"))
    )
    (net (code "63") (name "/VBUS SENSE") (class "Default")
      (node (ref "R11") (pin "2") (pinfunction "2_2") (pintype "passive"))
      (node (ref "R9") (pin "1") (pinfunction "1_1") (pintype "passive"))
      (node (ref "U2") (pin "16") (pinfunction "CBUS3_16") (pintype "passive"))
    )
    (net (code "64") (name "GND") (class "Default")
      (node (ref "C1") (pin "1") (pinfunction "1_1") (pintype "passive"))
      (node (ref "C10") (pin "1") (pinfunction "1_1") (pintype "passive"))
      (node (ref "C11") (pin "1") (pinfunction "1_1") (pintype "passive"))
      (node (ref "C12") (pin "1") (pinfunction "1_1") (pintype "passive"))
      (node (ref "C13") (pin "1") (pinfunction "1_1") (pintype "passive"))
      (node (ref "C14") (pin "1") (pinfunction "1_1") (pintype "passive"))
      (node (ref "C15") (pin "1") (pinfunction "1_1") (pintype "passive"))
      (node (ref "C16") (pin "1") (pinfunction "1_1") (pintype "passive"))
      (node (ref "C17") (pin "1") (pinfunction "1_1") (pintype "passive"))
      (node (ref "C2") (pin "1") (pinfunction "1_1") (pintype "passive"))
      (node (ref "C3") (pin "1") (pinfunction "1_1") (pintype "passive"))
      (node (ref "C4") (pin "1") (pinfunction "1_1") (pintype "passive"))
      (node (ref "C5") (pin "1") (pinfunction "1_1") (pintype "passive"))
      (node (ref "C6") (pin "1") (pinfunction "1_1") (pintype "passive"))
      (node (ref "C7") (pin "1") (pinfunction "1_1") (pintype "passive"))
      (node (ref "C8") (pin "1") (pinfunction "1_1") (pintype "passive"))
      (node (ref "C9") (pin "1") (pinfunction "1_1") (pintype "passive"))
      (node (ref "D2") (pin "1") (pinfunction "1_1") (pintype "passive"))
      (node (ref "D3") (pin "1") (pinfunction "1_1") (pintype "passive"))
      (node (ref "D4") (pin "1") (pinfunction "1_1") (pintype "passive"))
      (node (ref "D5") (pin "1") (pinfunction "1_1") (pintype "passive"))
      (node (ref "D6") (pin "1") (pinfunction "1_1") (pintype "passive"))
      (node (ref "D7") (pin "1") (pinfunction "1_1") (pintype "passive"))
      (node (ref "D8") (pin "1") (pinfunction "1_1") (pintype "passive"))
      (node (ref "J1") (pin "1") (pinfunction "1_1") (pintype "passive"))
      (node (ref "J1") (pin "23") (pinfunction "23_23") (pintype "passive"))
      (node (ref "J2") (pin "2") (pinfunction "2_2") (pintype "passive"))
      (node (ref "J2") (pin "24") (pinfunction "24_24") (pintype "passive"))
      (node (ref "J3") (pin "A1B12") (pinfunction "GND_A1B12_A1B12") (pintype "passive"))
      (node (ref "J3") (pin "B1A12") (pinfunction "GND_B1A12_B1A12") (pintype "passive"))
      (node (ref "J3") (pin "S1") (pinfunction "SHIELD_1_S1") (pintype "passive"))
      (node (ref "J3") (pin "S2") (pinfunction "SHIELD_2_S2") (pintype "passive"))
      (node (ref "J3") (pin "S3") (pinfunction "SHIELD_3_S3") (pintype "passive"))
      (node (ref "J3") (pin "S4") (pinfunction "SHIELD_4_S4") (pintype "passive"))
      (node (ref "J4") (pin "A1B12") (pinfunction "GND_A1B12_A1B12") (pintype "passive"))
      (node (ref "J4") (pin "B1A12") (pinfunction "GND_B1A12_B1A12") (pintype "passive"))
      (node (ref "J4") (pin "S1") (pinfunction "SHIELD_1_S1") (pintype "passive"))
      (node (ref "J4") (pin "S2") (pinfunction "SHIELD_2_S2") (pintype "passive"))
      (node (ref "J4") (pin "S3") (pinfunction "SHIELD_3_S3") (pintype "passive"))
      (node (ref "J4") (pin "S4") (pinfunction "SHIELD_4_S4") (pintype "passive"))
      (node (ref "R10") (pin "1") (pinfunction "1_1") (pintype "passive"))
      (node (ref "R11") (pin "1") (pinfunction "1_1") (pintype "passive"))
      (node (ref "R12") (pin "1") (pinfunction "1_1") (pintype "passive"))
      (node (ref "R13") (pin "1") (pinfunction "1_1") (pintype "passive"))
      (node (ref "R14") (pin "1") (pinfunction "1_1") (pintype "passive"))
      (node (ref "R15") (pin "1") (pinfunction "1_1") (pintype "passive"))
      (node (ref "U1") (pin "1") (pinfunction "GND_01_1") (pintype "passive"))
      (node (ref "U1") (pin "2") (pinfunction "GND_02_2") (pintype "passive"))
      (node (ref "U1") (pin "42") (pinfunction "GND_42") (pintype "passive"))
      (node (ref "U1") (pin "43") (pinfunction "GND_43") (pintype "passive"))
      (node (ref "U1") (pin "46") (pinfunction "GND_46_46") (pintype "passive"))
      (node (ref "U1") (pin "47") (pinfunction "GND_47_47") (pintype "passive"))
      (node (ref "U1") (pin "48") (pinfunction "GND_48_48") (pintype "passive"))
      (node (ref "U1") (pin "49") (pinfunction "GND_49_49") (pintype "passive"))
      (node (ref "U1") (pin "50") (pinfunction "GND_50_50") (pintype "passive"))
      (node (ref "U1") (pin "51") (pinfunction "GND_51_51") (pintype "passive"))
      (node (ref "U1") (pin "52") (pinfunction "GND_52_52") (pintype "passive"))
      (node (ref "U1") (pin "53") (pinfunction "GND_53_53") (pintype "passive"))
      (node (ref "U1") (pin "54") (pinfunction "GND_54_54") (pintype "passive"))
      (node (ref "U1") (pin "55") (pinfunction "GND_55_55") (pintype "passive"))
      (node (ref "U1") (pin "56") (pinfunction "GND_56_56") (pintype "passive"))
      (node (ref "U1") (pin "57") (pinfunction "GND_57_57") (pintype "passive"))
      (node (ref "U1") (pin "58") (pinfunction "GND_58_58") (pintype "passive"))
      (node (ref "U1") (pin "59") (pinfunction "GND_59_59") (pintype "passive"))
      (node (ref "U1") (pin "60") (pinfunction "GND_60_60") (pintype "passive"))
      (node (ref "U1") (pin "61") (pinfunction "GND_61_61") (pintype "passive"))
      (node (ref "U1") (pin "62") (pinfunction "GND_62_62") (pintype "passive"))
      (node (ref "U1") (pin "63") (pinfunction "GND_63_63") (pintype "passive"))
      (node (ref "U1") (pin "64") (pinfunction "GND_64_64") (pintype "passive"))
      (node (ref "U1") (pin "65") (pinfunction "GND_65_65") (pintype "passive"))
      (node (ref "U1") (pin "66") (pinfunction "GND_66_66") (pintype "passive"))
      (node (ref "U1") (pin "67") (pinfunction "GND_67_67") (pintype "passive"))
      (node (ref "U1") (pin "68") (pinfunction "GND_68_68") (pintype "passive"))
      (node (ref "U1") (pin "69") (pinfunction "GND_69_69") (pintype "passive"))
      (node (ref "U1") (pin "70") (pinfunction "GND_70_70") (pintype "passive"))
      (node (ref "U1") (pin "71") (pinfunction "GND_71_71") (pintype "passive"))
      (node (ref "U1") (pin "72") (pinfunction "GND_72_72") (pintype "passive"))
      (node (ref "U1") (pin "73") (pinfunction "GND_73_73") (pintype "passive"))
      (node (ref "U2") (pin "13") (pinfunction "GND_13") (pintype "passive"))
      (node (ref "U2") (pin "21") (pinfunction "GND_21") (pintype "passive"))
      (node (ref "U2") (pin "3") (pinfunction "GND_3") (pintype "passive"))
      (node (ref "U3") (pin "2") (pinfunction "GND_2") (pintype "power_in"))
      (node (ref "U3") (pin "4") (pinfunction "GND_4") (pintype "power_in"))
      (node (ref "sw1") (pin "3") (pinfunction "3_3") (pintype "passive"))
      (node (ref "sw1") (pin "4") (pinfunction "4_4") (pintype "passive"))
      (node (ref "sw2") (pin "3") (pinfunction "3_3") (pintype "passive"))
      (node (ref "sw2") (pin "4") (pinfunction "4_4") (pintype "passive"))
    )
    (net (code "65") (name "Net-(D1-Pad2)") (class "Default")
      (node (ref "D1") (pin "2") (pinfunction "2_2") (pintype "passive"))
      (node (ref "R3") (pin "1") (pinfunction "1_1") (pintype "passive"))
    )
    (net (code "66") (name "Net-(D2-Pad2)") (class "Default")
      (node (ref "D2") (pin "2") (pinfunction "2_2") (pintype "passive"))
      (node (ref "R5") (pin "1") (pinfunction "1_1") (pintype "passive"))
    )
    (net (code "67") (name "Net-(J3-CC1)") (class "Default")
      (node (ref "J3") (pin "A5") (pinfunction "CC1_A5") (pintype "passive"))
      (node (ref "R13") (pin "2") (pinfunction "2_2") (pintype "passive"))
    )
    (net (code "68") (name "Net-(J3-CC2)") (class "Default")
      (node (ref "J3") (pin "B5") (pinfunction "CC2_B5") (pintype "passive"))
      (node (ref "R12") (pin "2") (pinfunction "2_2") (pintype "passive"))
    )
    (net (code "69") (name "Net-(J4-CC1)") (class "Default")
      (node (ref "J4") (pin "A5") (pinfunction "CC1_A5") (pintype "passive"))
      (node (ref "R15") (pin "2") (pinfunction "2_2") (pintype "passive"))
    )
    (net (code "70") (name "Net-(J4-CC2)") (class "Default")
      (node (ref "J4") (pin "B5") (pinfunction "CC2_B5") (pintype "passive"))
      (node (ref "R14") (pin "2") (pinfunction "2_2") (pintype "passive"))
    )
    (net (code "71") (name "Net-(Q1-B)") (class "Default")
      (node (ref "Q1") (pin "1") (pinfunction "B_1") (pintype "passive"))
      (node (ref "R21") (pin "1") (pinfunction "1_1") (pintype "passive"))
    )
    (net (code "72") (name "Net-(Q2-B)") (class "Default")
      (node (ref "Q2") (pin "1") (pinfunction "B_1") (pintype "passive"))
      (node (ref "R23") (pin "1") (pinfunction "1_1") (pintype "passive"))
    )
    (net (code "73") (name "Net-(U2-CBUS0)") (class "Default")
      (node (ref "R10") (pin "2") (pinfunction "2_2") (pintype "passive"))
      (node (ref "U2") (pin "15") (pinfunction "CBUS0_15") (pintype "passive"))
    )
    (net (code "74") (name "unconnected-(J1-Pad24)") (class "Default")
      (node (ref "J1") (pin "24") (pinfunction "24_24") (pintype "passive+no_connect"))
    )
    (net (code "75") (name "unconnected-(J3-SBU1-PadA8)") (class "Default")
      (node (ref "J3") (pin "A8") (pinfunction "SBU1_A8") (pintype "passive+no_connect"))
    )
    (net (code "76") (name "unconnected-(J3-SBU2-PadB8)") (class "Default")
      (node (ref "J3") (pin "B8") (pinfunction "SBU2_B8") (pintype "passive+no_connect"))
    )
    (net (code "77") (name "unconnected-(J4-SBU1-PadA8)") (class "Default")
      (node (ref "J4") (pin "A8") (pinfunction "SBU1_A8") (pintype "passive"))
    )
    (net (code "78") (name "unconnected-(J4-SBU2-PadB8)") (class "Default")
      (node (ref "J4") (pin "B8") (pinfunction "SBU2_B8") (pintype "passive"))
    )
    (net (code "79") (name "unconnected-(U2-CBUS1-Pad14)") (class "Default")
      (node (ref "U2") (pin "14") (pinfunction "CBUS1_14") (pintype "passive+no_connect"))
    )
    (net (code "80") (name "unconnected-(U2-CBUS2-Pad7)") (class "Default")
      (node (ref "U2") (pin "7") (pinfunction "CBUS2_7") (pintype "passive+no_connect"))
    )
    (net (code "81") (name "unconnected-(U2-~{CTS}-Pad6)") (class "Default")
      (node (ref "U2") (pin "6") (pinfunction "~{CTS}_6") (pintype "passive+no_connect"))
    )
    (net (code "82") (name "unconnected-(U2-~{DCD}-Pad5)") (class "Default")
      (node (ref "U2") (pin "5") (pinfunction "~{DCD}_5") (pintype "passive+no_connect"))
    )
    (net (code "83") (name "unconnected-(U2-~{DSR}-Pad4)") (class "Default")
      (node (ref "U2") (pin "4") (pinfunction "~{DSR}_4") (pintype "passive+no_connect"))
    )
    (net (code "84") (name "unconnected-(U2-~{RI}-Pad2)") (class "Default")
      (node (ref "U2") (pin "2") (pinfunction "~{RI}_2") (pintype "passive+no_connect"))
    )
  )
)
